# REALY_AND_PRESSURE.net
KiCad netlist of a schematic drawn in Altium Designer
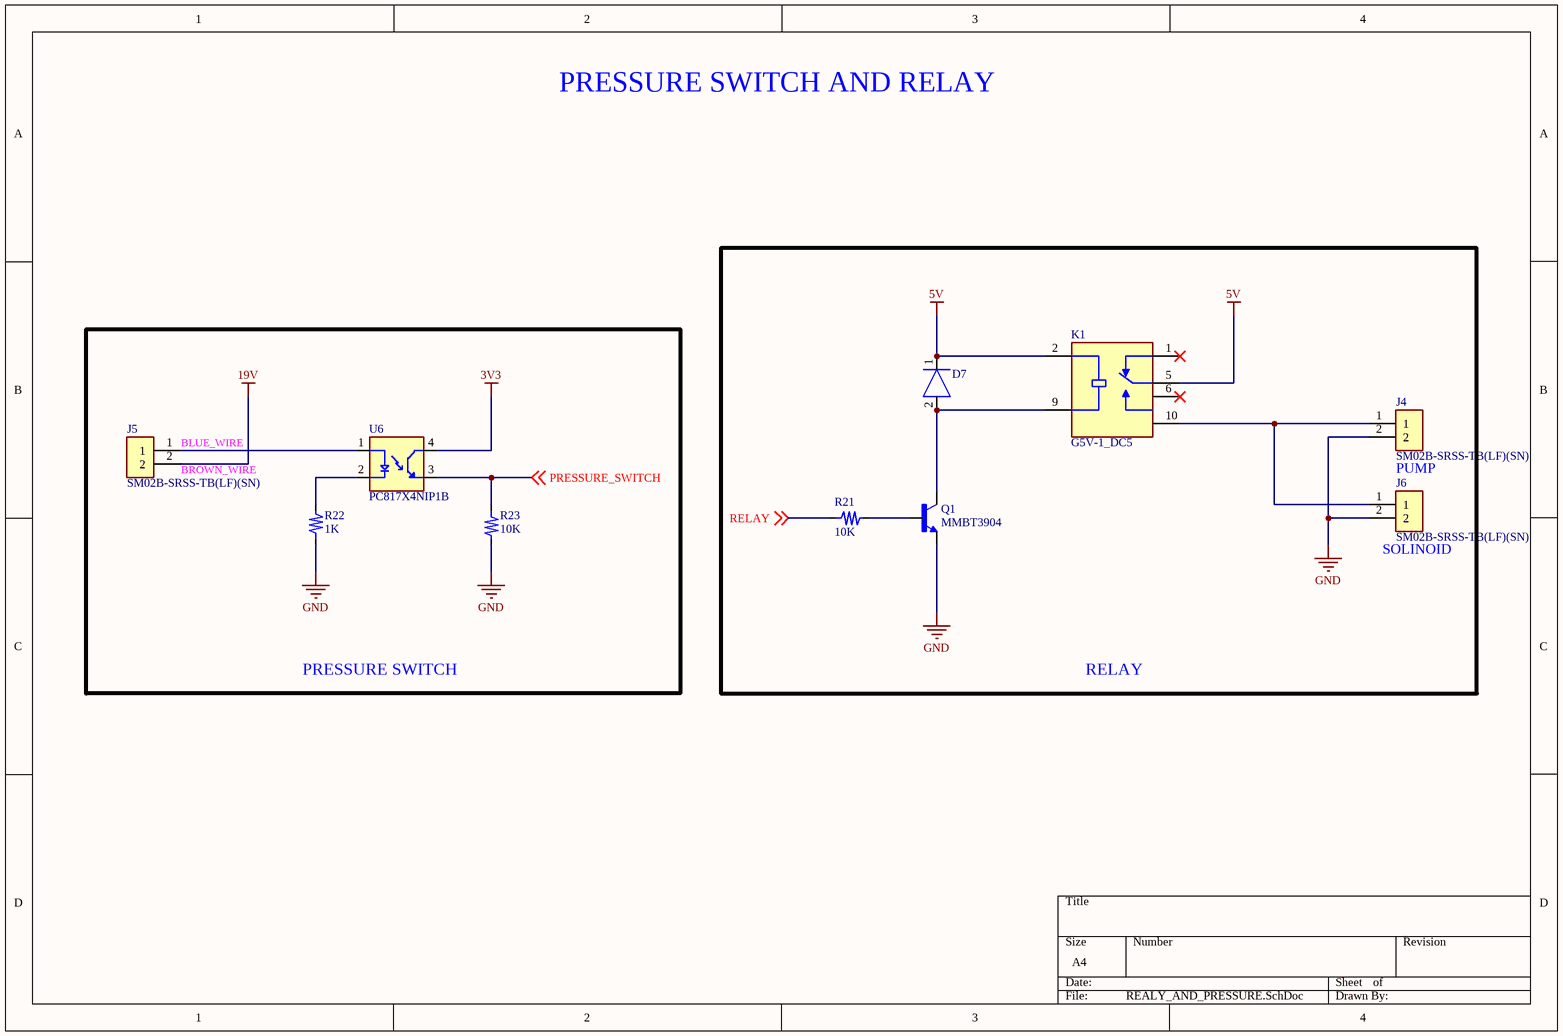
[diagram p0: REALY_AND_PRESSURE.SchDoc]

(export (version "E")
  (design (tool "Eeschema 10.0.6"))
  (components
    (comp (ref "D7")
      (value "Diode")
      (footprint "RELAY DIODE")
      (fields (field (name "PART NUMBER") "1N4002"))
      (libsource (lib "Schlib2") (part "Diode"))
    )
    (comp (ref "J4")
      (value "SM02B-SRSS-TB(LF)(SN)")
      (footprint "JST_BM02B-SRSS-TB(LF)(SN)")
      (description "Connector Header Surface Mount, Right Angle 2 position 0.039 (1.00mm)")
      (fields (field (name "PART NUMBER") "BM02B-SRSS-TB(LF)(SN)"))
      (libsource (lib "") (part "SM02B-SRSS-TB(LF)(SN)_1"))
    )
    (comp (ref "J5")
      (value "SM02B-SRSS-TB(LF)(SN)")
      (footprint "JST_BM02B-SRSS-TB(LF)(SN)")
      (description "Connector Header Surface Mount, Right Angle 2 position 0.039 (1.00mm)")
      (fields (field (name "PART NUMBER") "BM02B-SRSS-TB(LF)(SN)"))
      (libsource (lib "Schlib2") (part "SM02B-SRSS-TB(LF)(SN)"))
    )
    (comp (ref "J6")
      (value "SM02B-SRSS-TB(LF)(SN)")
      (footprint "JST_BM02B-SRSS-TB(LF)(SN)")
      (description "Connector Header Surface Mount, Right Angle 2 position 0.039 (1.00mm)")
      (fields (field (name "PART NUMBER") "BM02B-SRSS-TB(LF)(SN)"))
      (libsource (lib "") (part "SM02B-SRSS-TB(LF)(SN)_1"))
    )
    (comp (ref "K1")
      (value "G5V-1_DC5")
      (footprint "RELAY_G5V-1_DC5")
      (description "General Purpose Relay SPDT (1 Form C) Through Hole")
      (fields (field (name "PART NUMBER") "G5V-1 DC5"))
      (libsource (lib "Schlib2") (part "G5V-1_DC5"))
    )
    (comp (ref "Q1")
      (value "MMBT3904")
      (footprint "TRANS_MMBT3904")
      (description "BJT, SOT-23, 40V, 200mA, NPN, 0.35W, 150Â°C")
      (fields (field (name "PART NUMBER") "MMBT3904(RANGE:100-300)"))
      (libsource (lib "Schlib2") (part "MMBT3904"))
    )
    (comp (ref "R21")
      (value "10K")
      (footprint "RES 0603")
      (fields (field (name "PART NUMBER") "RS-03K103JT"))
      (libsource (lib "Schlib2") (part "Resistor"))
    )
    (comp (ref "R22")
      (value "1K")
      (footprint "RES 0603")
      (fields (field (name "PART NUMBER") "RS-03K102JT"))
      (libsource (lib "Schlib2") (part "Resistor"))
    )
    (comp (ref "R23")
      (value "10K")
      (footprint "RES 0603")
      (fields (field (name "PART NUMBER") "RS-03K103JT"))
      (libsource (lib "Schlib2") (part "Resistor"))
    )
    (comp (ref "U6")
      (value "PC817X4NIP1B")
      (footprint "SOIC254P960X420-4N")
      (description "Optocoupler DC-IN 1-CH Transistor DC-OUT 4-Pin DIP SMD T/R")
      (fields (field (name "PART NUMBER") "PC817X3NIP1B"))
      (libsource (lib "Schlib2") (part "PC817X4NIP1B"))
    )
  )
  (nets
    (net (code "1") (name "3V3") (class "Default")
      (node (ref "U6") (pin "4") (pinfunction "CT_4") (pintype "passive"))
    )
    (net (code "2") (name "5V") (class "Default")
      (node (ref "D7") (pin "1") (pinfunction "1_1") (pintype "passive"))
      (node (ref "K1") (pin "2") (pinfunction "COIL1_2") (pintype "passive"))
      (node (ref "K1") (pin "5") (pinfunction "COM_5") (pintype "passive"))
    )
    (net (code "3") (name "19V") (class "Default")
      (node (ref "J5") (pin "2") (pinfunction "2_2") (pintype "passive"))
    )
    (net (code "4") (name "GND") (class "Default")
      (node (ref "J4") (pin "2") (pinfunction "2_2") (pintype "passive"))
      (node (ref "J6") (pin "2") (pinfunction "2_2") (pintype "passive"))
      (node (ref "Q1") (pin "2") (pinfunction "E_2") (pintype "passive"))
      (node (ref "R22") (pin "1") (pinfunction "1_1") (pintype "passive"))
      (node (ref "R23") (pin "2") (pinfunction "2_2") (pintype "passive"))
    )
    (net (code "5") (name "Net-(K1-COIL2)") (class "Default")
      (node (ref "D7") (pin "2") (pinfunction "2_2") (pintype "passive"))
      (node (ref "K1") (pin "9") (pinfunction "COIL2_9") (pintype "passive"))
      (node (ref "Q1") (pin "3") (pinfunction "C_3") (pintype "passive"))
    )
    (net (code "6") (name "Net-(K1-NO)") (class "Default")
      (node (ref "J4") (pin "1") (pinfunction "1_1") (pintype "passive"))
      (node (ref "J6") (pin "1") (pinfunction "1_1") (pintype "passive"))
      (node (ref "K1") (pin "10") (pinfunction "NO_10") (pintype "passive"))
    )
    (net (code "7") (name "Net-(Q1-B)") (class "Default")
      (node (ref "Q1") (pin "1") (pinfunction "B_1") (pintype "passive"))
      (node (ref "R21") (pin "2") (pinfunction "2_2") (pintype "passive"))
    )
    (net (code "8") (name "Net-(U6-A)") (class "Default")
      (node (ref "J5") (pin "1") (pinfunction "1_1") (pintype "passive"))
      (node (ref "U6") (pin "1") (pinfunction "A_1") (pintype "passive"))
    )
    (net (code "9") (name "Net-(U6-C)") (class "Default")
      (node (ref "R22") (pin "2") (pinfunction "2_2") (pintype "passive"))
      (node (ref "U6") (pin "2") (pinfunction "C_2") (pintype "passive"))
    )
    (net (code "10") (name "PRESSURE_SWITCH") (class "Default")
      (node (ref "R23") (pin "1") (pinfunction "1_1") (pintype "passive"))
      (node (ref "U6") (pin "3") (pinfunction "ET_3") (pintype "passive"))
    )
    (net (code "11") (name "RELAY") (class "Default")
      (node (ref "R21") (pin "1") (pinfunction "1_1") (pintype "passive"))
    )
    (net (code "12") (name "unconnected-(K1-COM-Pad6)") (class "Default")
      (node (ref "K1") (pin "6") (pinfunction "COM_6") (pintype "passive+no_connect"))
    )
    (net (code "13") (name "unconnected-(K1-NC-Pad1)") (class "Default")
      (node (ref "K1") (pin "1") (pinfunction "NC_1") (pintype "passive+no_connect"))
    )
  )
)
